# power_supply.net
KiCad netlist of a schematic drawn in Altium Designer
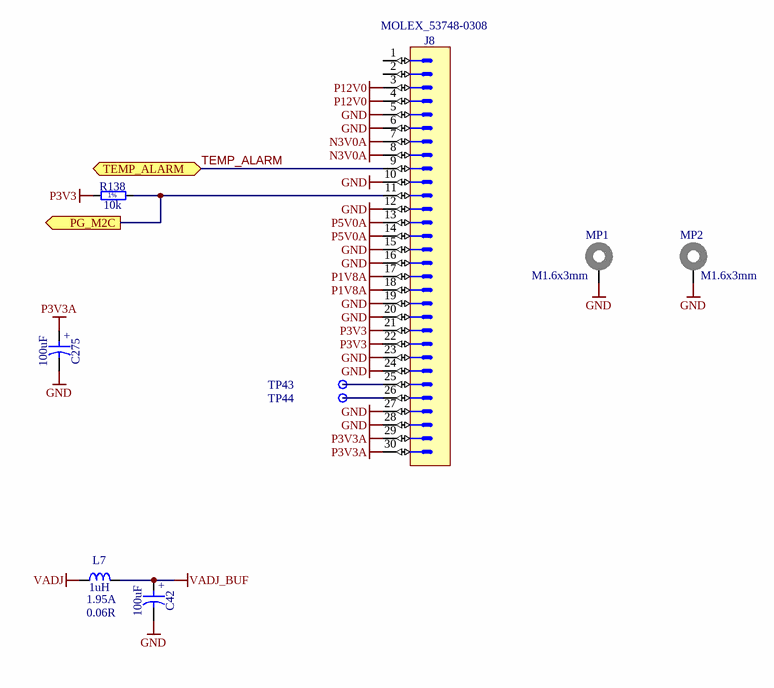
[diagram p0: power_supply.SchDoc]

(export (version "E")
  (design (tool "Eeschema 10.0.6"))
  (components
    (comp (ref "C42")
      (value "100uF")
      (footprint "CAPMP3216X180N")
      (description "Polarised capacitor")
      (fields
        (field (name "PART NUMBER") "CTE3216-18_100UF_6.3V_20%_ESR0500_AVX_TLJ")
        (field (name "VOLTAGE") "6.3V")
        (field (name "AUTHOR") "CERN DEM JLC")
      )
      (libsource (lib "Capacitors") (part "Capacitor - polarized"))
    )
    (comp (ref "C275")
      (value "100uF")
      (footprint "CAPMP3216X180N")
      (description "Polarised capacitor")
      (fields
        (field (name "PART NUMBER") "CTE3216-18_100UF_6.3V_20%_ESR0500_AVX_TLJ")
        (field (name "VOLTAGE") "6.3V")
        (field (name "AUTHOR") "CERN DEM JLC")
      )
      (libsource (lib "Capacitors") (part "Capacitor - polarized"))
    )
    (comp (ref "J8")
      (value "SlimStack™")
      (footprint "MOLEX_53748-0308")
      (description "Connector 30 Male")
      (fields
        (field (name "PART NUMBER") "MOLEX_53748-0308")
        (field (name "MANUFACTURER") "MOLEX")
        (field (name "AUTHOR") "CERN DEM JLC")
      )
      (libsource (lib "Connectors") (part "Connector 30 Male"))
    )
    (comp (ref "L7")
      (value "1uH")
      (footprint "INDC2620X100N")
      (description "Inductor")
      (fields
        (field (name "PART NUMBER") "IND1008_1UH_20%_WURTH_74479787210B")
        (field (name "POWER") "1.95A")
        (field (name "RESISTANCE") "0.06R")
        (field (name "TOLERANCE") "±20%")
        (field (name "AUTHOR") "CERN DEM JLC")
      )
      (libsource (lib "Inductors & Transformers") (part "Inductor"))
    )
    (comp (ref "MP1")
      (value "M1.6x3mm")
      (footprint "9774030633")
      (description "WA-SMSI SMT Steel Spacer, M1.6 Thread Internal, OD 3.3mm, M1.6x3mm")
      (fields
        (field (name "MANUFACTURER PART NUMBER") "9774030633R")
        (field (name "MANUFACTURER") "Wurth Elektronik")
      )
      (libsource (lib "9774015633R_Altium_SMSI_rev20c") (part "9774030633R"))
    )
    (comp (ref "MP2")
      (value "M1.6x3mm")
      (footprint "9774030633")
      (description "WA-SMSI SMT Steel Spacer, M1.6 Thread Internal, OD 3.3mm, M1.6x3mm")
      (fields
        (field (name "MANUFACTURER PART NUMBER") "9774030633R")
        (field (name "MANUFACTURER") "Wurth Elektronik")
      )
      (libsource (lib "9774015633R_Altium_SMSI_rev20c") (part "9774030633R"))
    )
    (comp (ref "R138")
      (value "10k")
      (footprint "RESC1005X40N")
      (description "Resistor - 1%")
      (fields
        (field (name "PART NUMBER") "R0402_10K_1%_0.0625W_100PPM")
        (field (name "POWER") "0.0625W")
        (field (name "AUTHOR") "CERN DEM JLC")
      )
      (libsource (lib "Resistors") (part "Resistor - 1%"))
    )
    (comp (ref "TP43")
      (value "Test Point")
      (footprint "TPS127")
      (fields (field (name "PART NUMBER") "SMD_PAD_1.27X1.27MM") (field (name "AUTHOR") "CERN DEM JLC"))
      (libsource (lib "Eletro-mechanical") (part "Test Point"))
    )
    (comp (ref "TP44")
      (value "Test Point")
      (footprint "TPS127")
      (fields (field (name "PART NUMBER") "SMD_PAD_1.27X1.27MM") (field (name "AUTHOR") "CERN DEM JLC"))
      (libsource (lib "Eletro-mechanical") (part "Test Point"))
    )
  )
  (nets
    (net (code "1") (name "/PG_M2C") (class "Default")
      (node (ref "J8") (pin "11") (pinfunction "11_11") (pintype "bidirectional"))
      (node (ref "R138") (pin "2") (pinfunction "2_2") (pintype "passive"))
    )
    (net (code "2") (name "/TEMP_ALARM") (class "Default")
      (node (ref "J8") (pin "9") (pinfunction "9_9") (pintype "bidirectional"))
    )
    (net (code "3") (name "GND") (class "Default")
      (node (ref "C275") (pin "2") (pinfunction "2_2") (pintype "passive"))
      (node (ref "C42") (pin "2") (pinfunction "2_2") (pintype "passive"))
      (node (ref "J8") (pin "10") (pinfunction "10_10") (pintype "bidirectional"))
      (node (ref "J8") (pin "12") (pinfunction "12_12") (pintype "bidirectional"))
      (node (ref "J8") (pin "15") (pinfunction "15_15") (pintype "bidirectional"))
      (node (ref "J8") (pin "16") (pinfunction "16_16") (pintype "bidirectional"))
      (node (ref "J8") (pin "19") (pinfunction "19_19") (pintype "bidirectional"))
      (node (ref "J8") (pin "20") (pinfunction "20_20") (pintype "bidirectional"))
      (node (ref "J8") (pin "23") (pinfunction "23_23") (pintype "bidirectional"))
      (node (ref "J8") (pin "24") (pinfunction "24_24") (pintype "bidirectional"))
      (node (ref "J8") (pin "27") (pinfunction "27_27") (pintype "bidirectional"))
      (node (ref "J8") (pin "28") (pinfunction "28_28") (pintype "bidirectional"))
      (node (ref "J8") (pin "5") (pinfunction "5_5") (pintype "bidirectional"))
      (node (ref "J8") (pin "6") (pinfunction "6_6") (pintype "bidirectional"))
      (node (ref "MP1") (pin "1") (pinfunction "1_1") (pintype "passive"))
      (node (ref "MP2") (pin "1") (pinfunction "1_1") (pintype "passive"))
    )
    (net (code "4") (name "N3V0A") (class "Default")
      (node (ref "J8") (pin "7") (pinfunction "7_7") (pintype "bidirectional"))
      (node (ref "J8") (pin "8") (pinfunction "8_8") (pintype "bidirectional"))
    )
    (net (code "5") (name "Net-(J8-Pad25)") (class "Default")
      (node (ref "J8") (pin "25") (pinfunction "25_25") (pintype "bidirectional"))
      (node (ref "TP43") (pin "1") (pinfunction "1_1") (pintype "bidirectional"))
    )
    (net (code "6") (name "Net-(J8-Pad26)") (class "Default")
      (node (ref "J8") (pin "26") (pinfunction "26_26") (pintype "bidirectional"))
      (node (ref "TP44") (pin "1") (pinfunction "1_1") (pintype "bidirectional"))
    )
    (net (code "7") (name "P1V8A") (class "Default")
      (node (ref "J8") (pin "17") (pinfunction "17_17") (pintype "bidirectional"))
      (node (ref "J8") (pin "18") (pinfunction "18_18") (pintype "bidirectional"))
    )
    (net (code "8") (name "P3V3") (class "Default")
      (node (ref "J8") (pin "21") (pinfunction "21_21") (pintype "bidirectional"))
      (node (ref "J8") (pin "22") (pinfunction "22_22") (pintype "bidirectional"))
      (node (ref "R138") (pin "1") (pinfunction "1_1") (pintype "passive"))
    )
    (net (code "9") (name "P3V3A") (class "Default")
      (node (ref "C275") (pin "1") (pinfunction "1_1") (pintype "passive"))
      (node (ref "J8") (pin "29") (pinfunction "29_29") (pintype "bidirectional"))
      (node (ref "J8") (pin "30") (pinfunction "30_30") (pintype "bidirectional"))
    )
    (net (code "10") (name "P5V0A") (class "Default")
      (node (ref "J8") (pin "13") (pinfunction "13_13") (pintype "bidirectional"))
      (node (ref "J8") (pin "14") (pinfunction "14_14") (pintype "bidirectional"))
    )
    (net (code "11") (name "P12V0") (class "Default")
      (node (ref "J8") (pin "3") (pinfunction "3_3") (pintype "bidirectional"))
      (node (ref "J8") (pin "4") (pinfunction "4_4") (pintype "bidirectional"))
    )
    (net (code "12") (name "VADJ") (class "Default")
      (node (ref "L7") (pin "1") (pinfunction "1_1") (pintype "passive"))
    )
    (net (code "13") (name "VADJ_BUF") (class "Default")
      (node (ref "C42") (pin "1") (pinfunction "1_1") (pintype "passive"))
      (node (ref "L7") (pin "2") (pinfunction "2_2") (pintype "passive"))
    )
    (net (code "14") (name "unconnected-(J8-Pad1)") (class "Default")
      (node (ref "J8") (pin "1") (pinfunction "1_1") (pintype "bidirectional"))
    )
    (net (code "15") (name "unconnected-(J8-Pad2)") (class "Default")
      (node (ref "J8") (pin "2") (pinfunction "2_2") (pintype "bidirectional"))
    )
  )
)
